# SensorRPM.net
KiCad netlist of a schematic drawn in Altium Designer
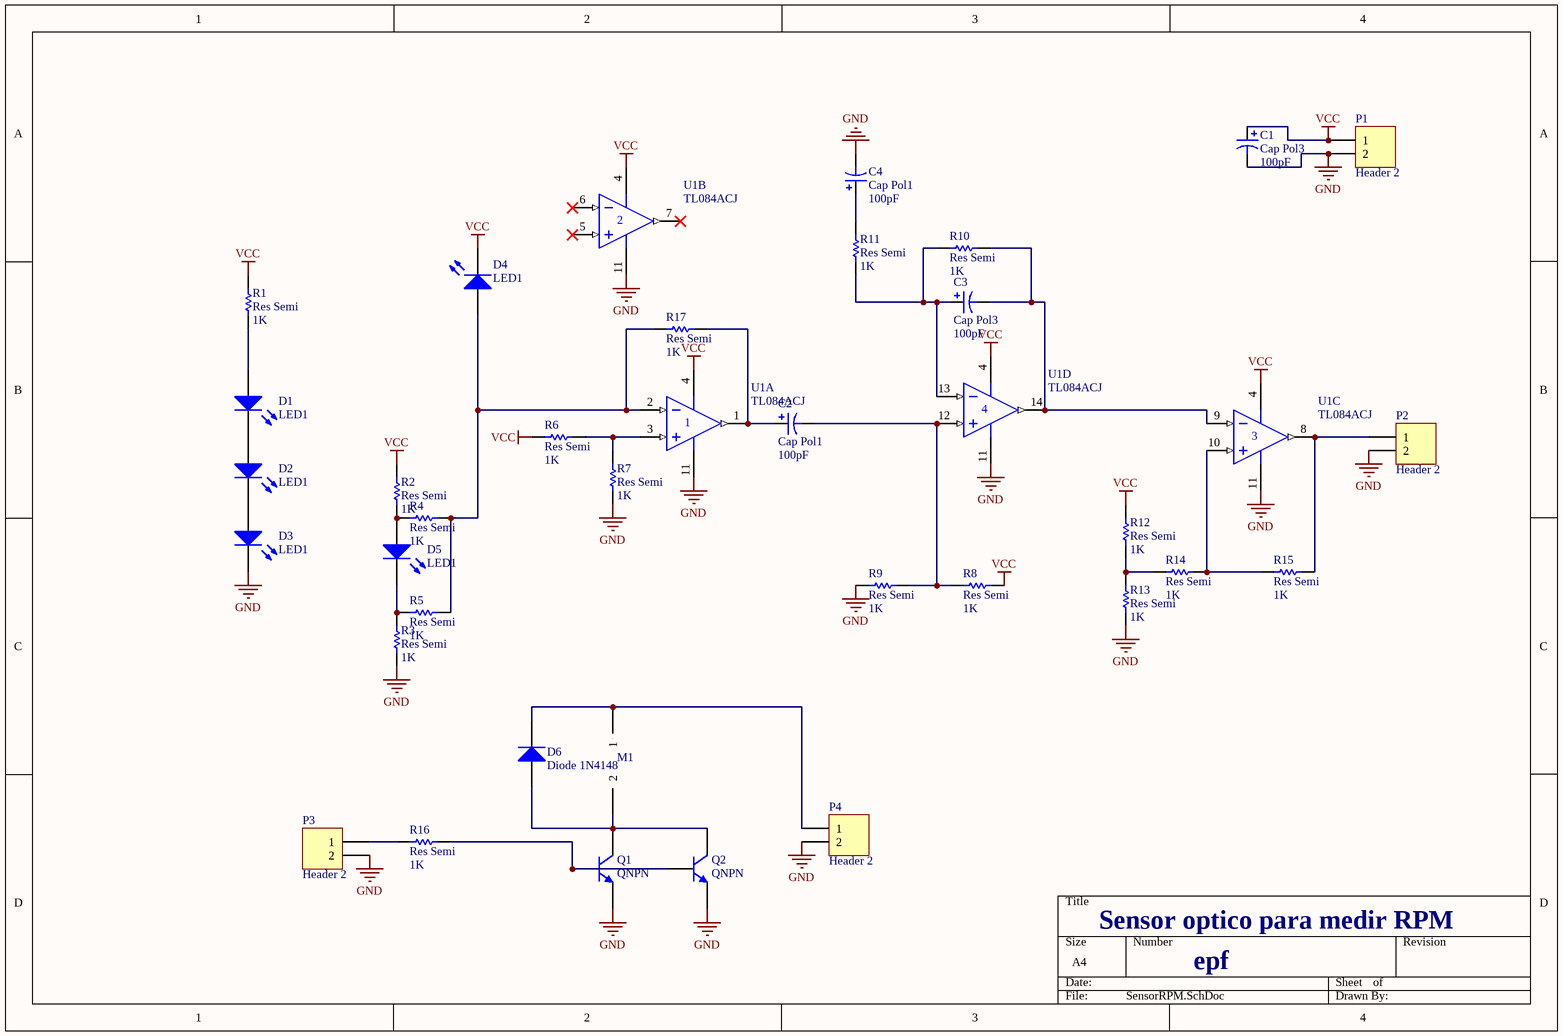
[diagram p0: SensorRPM.SchDoc]

(export (version "E")
  (design (tool "Eeschema 10.0.6"))
  (components
    (comp (ref "C1")
      (value "Cap Pol3")
      (footprint "C0805")
      (description "Polarized Capacitor (Surface Mount)")
      (fields (field (name "ALTIUM_VALUE") "100pF") (field (name "PUBLISHER") "Altium Limited"))
      (libsource (lib "Miscellaneous Devices") (part "Cap Pol3"))
    )
    (comp (ref "C2")
      (value "Cap Pol1")
      (footprint "B")
      (description "Polarized Capacitor (Radial)")
      (fields (field (name "ALTIUM_VALUE") "100pF") (field (name "PUBLISHER") "Altium Limited"))
      (libsource (lib "Miscellaneous Devices") (part "Cap Pol1"))
    )
    (comp (ref "C3")
      (value "Cap Pol3")
      (footprint "C0805")
      (description "Polarized Capacitor (Surface Mount)")
      (fields (field (name "ALTIUM_VALUE") "100pF") (field (name "PUBLISHER") "Altium Limited"))
      (libsource (lib "Miscellaneous Devices") (part "Cap Pol3"))
    )
    (comp (ref "C4")
      (value "Cap Pol1")
      (footprint "B")
      (description "Polarized Capacitor (Radial)")
      (fields (field (name "ALTIUM_VALUE") "100pF") (field (name "PUBLISHER") "Altium Limited"))
      (libsource (lib "Miscellaneous Devices") (part "Cap Pol1"))
    )
    (comp (ref "D1")
      (value "LED1")
      (footprint "LED-1")
      (description "Typical RED GaAs LED")
      (fields (field (name "PUBLISHER") "Altium Limited"))
      (libsource (lib "Miscellaneous Devices") (part "LED1"))
    )
    (comp (ref "D2")
      (value "LED1")
      (footprint "LED-1")
      (description "Typical RED GaAs LED")
      (fields (field (name "PUBLISHER") "Altium Limited"))
      (libsource (lib "Miscellaneous Devices") (part "LED1"))
    )
    (comp (ref "D3")
      (value "LED1")
      (footprint "LED-1")
      (description "Typical RED GaAs LED")
      (fields (field (name "PUBLISHER") "Altium Limited"))
      (libsource (lib "Miscellaneous Devices") (part "LED1"))
    )
    (comp (ref "D4")
      (value "LED1")
      (footprint "LED-1")
      (description "Typical RED GaAs LED")
      (fields (field (name "PUBLISHER") "Altium Limited"))
      (libsource (lib "Miscellaneous Devices") (part "LED1"))
    )
    (comp (ref "D5")
      (value "LED1")
      (footprint "LED-1")
      (description "Typical RED GaAs LED")
      (fields (field (name "PUBLISHER") "Altium Limited"))
      (libsource (lib "Miscellaneous Devices") (part "LED1"))
    )
    (comp (ref "D6")
      (value "Diode 1N4148")
      (footprint "DO-35")
      (description "High Conductance Fast Diode")
      (fields (field (name "PUBLISHER") "Altium Limited"))
      (libsource (lib "Miscellaneous Devices") (part "Diode 1N4148"))
    )
    (comp (ref "M1") (value "Motor") (footprint "Motor1") (libsource (lib "epf") (part "Motor")))
    (comp (ref "P1")
      (value "Header 2")
      (footprint "HDR1X2")
      (description "Header, 2-Pin")
      (fields (field (name "PUBLISHER") "Altium Limited"))
      (libsource (lib "Miscellaneous Connectors") (part "Header 2"))
    )
    (comp (ref "P2")
      (value "Header 2")
      (footprint "HDR1X2")
      (description "Header, 2-Pin")
      (fields (field (name "PUBLISHER") "Altium Limited"))
      (libsource (lib "Miscellaneous Connectors") (part "Header 2"))
    )
    (comp (ref "P3")
      (value "Header 2")
      (footprint "HDR1X2")
      (description "Header, 2-Pin")
      (fields (field (name "PUBLISHER") "Altium Limited"))
      (libsource (lib "") (part "Header 2_1"))
    )
    (comp (ref "P4")
      (value "Header 2")
      (footprint "HDR1X2")
      (description "Header, 2-Pin")
      (fields (field (name "PUBLISHER") "Altium Limited"))
      (libsource (lib "Miscellaneous Connectors") (part "Header 2"))
    )
    (comp (ref "Q1")
      (value "QNPN")
      (footprint "SOT-23B")
      (description "NPN Bipolar Transistor")
      (fields (field (name "PUBLISHER") "Altium Limited"))
      (libsource (lib "Miscellaneous Devices") (part "QNPN"))
    )
    (comp (ref "Q2")
      (value "QNPN")
      (footprint "SOT-23B")
      (description "NPN Bipolar Transistor")
      (fields (field (name "PUBLISHER") "Altium Limited"))
      (libsource (lib "Miscellaneous Devices") (part "QNPN"))
    )
    (comp (ref "R1")
      (value "Res Semi")
      (footprint "2012[0805]")
      (description "Semiconductor Resistor")
      (fields (field (name "ALTIUM_VALUE") "1K") (field (name "PUBLISHER") "Altium Limited"))
      (libsource (lib "Miscellaneous Devices") (part "Res Semi"))
    )
    (comp (ref "R2")
      (value "Res Semi")
      (footprint "2012[0805]")
      (description "Semiconductor Resistor")
      (fields (field (name "ALTIUM_VALUE") "1K") (field (name "PUBLISHER") "Altium Limited"))
      (libsource (lib "Miscellaneous Devices") (part "Res Semi"))
    )
    (comp (ref "R3")
      (value "Res Semi")
      (footprint "2012[0805]")
      (description "Semiconductor Resistor")
      (fields (field (name "ALTIUM_VALUE") "1K") (field (name "PUBLISHER") "Altium Limited"))
      (libsource (lib "Miscellaneous Devices") (part "Res Semi"))
    )
    (comp (ref "R4")
      (value "Res Semi")
      (footprint "2012[0805]")
      (description "Semiconductor Resistor")
      (fields (field (name "ALTIUM_VALUE") "1K") (field (name "PUBLISHER") "Altium Limited"))
      (libsource (lib "Miscellaneous Devices") (part "Res Semi"))
    )
    (comp (ref "R5")
      (value "Res Semi")
      (footprint "2012[0805]")
      (description "Semiconductor Resistor")
      (fields (field (name "ALTIUM_VALUE") "1K") (field (name "PUBLISHER") "Altium Limited"))
      (libsource (lib "Miscellaneous Devices") (part "Res Semi"))
    )
    (comp (ref "R6")
      (value "Res Semi")
      (footprint "2012[0805]")
      (description "Semiconductor Resistor")
      (fields (field (name "ALTIUM_VALUE") "1K") (field (name "PUBLISHER") "Altium Limited"))
      (libsource (lib "Miscellaneous Devices") (part "Res Semi"))
    )
    (comp (ref "R7")
      (value "Res Semi")
      (footprint "2012[0805]")
      (description "Semiconductor Resistor")
      (fields (field (name "ALTIUM_VALUE") "1K") (field (name "PUBLISHER") "Altium Limited"))
      (libsource (lib "Miscellaneous Devices") (part "Res Semi"))
    )
    (comp (ref "R8")
      (value "Res Semi")
      (footprint "2012[0805]")
      (description "Semiconductor Resistor")
      (fields (field (name "ALTIUM_VALUE") "1K") (field (name "PUBLISHER") "Altium Limited"))
      (libsource (lib "Miscellaneous Devices") (part "Res Semi"))
    )
    (comp (ref "R9")
      (value "Res Semi")
      (footprint "2012[0805]")
      (description "Semiconductor Resistor")
      (fields (field (name "ALTIUM_VALUE") "1K") (field (name "PUBLISHER") "Altium Limited"))
      (libsource (lib "Miscellaneous Devices") (part "Res Semi"))
    )
    (comp (ref "R10")
      (value "Res Semi")
      (footprint "2012[0805]")
      (description "Semiconductor Resistor")
      (fields (field (name "ALTIUM_VALUE") "1K") (field (name "PUBLISHER") "Altium Limited"))
      (libsource (lib "Miscellaneous Devices") (part "Res Semi"))
    )
    (comp (ref "R11")
      (value "Res Semi")
      (footprint "2012[0805]")
      (description "Semiconductor Resistor")
      (fields (field (name "ALTIUM_VALUE") "1K") (field (name "PUBLISHER") "Altium Limited"))
      (libsource (lib "Miscellaneous Devices") (part "Res Semi"))
    )
    (comp (ref "R12")
      (value "Res Semi")
      (footprint "2012[0805]")
      (description "Semiconductor Resistor")
      (fields (field (name "ALTIUM_VALUE") "1K") (field (name "PUBLISHER") "Altium Limited"))
      (libsource (lib "Miscellaneous Devices") (part "Res Semi"))
    )
    (comp (ref "R13")
      (value "Res Semi")
      (footprint "2012[0805]")
      (description "Semiconductor Resistor")
      (fields (field (name "ALTIUM_VALUE") "1K") (field (name "PUBLISHER") "Altium Limited"))
      (libsource (lib "Miscellaneous Devices") (part "Res Semi"))
    )
    (comp (ref "R14")
      (value "Res Semi")
      (footprint "2012[0805]")
      (description "Semiconductor Resistor")
      (fields (field (name "ALTIUM_VALUE") "1K") (field (name "PUBLISHER") "Altium Limited"))
      (libsource (lib "Miscellaneous Devices") (part "Res Semi"))
    )
    (comp (ref "R15")
      (value "Res Semi")
      (footprint "2012[0805]")
      (description "Semiconductor Resistor")
      (fields (field (name "ALTIUM_VALUE") "1K") (field (name "PUBLISHER") "Altium Limited"))
      (libsource (lib "Miscellaneous Devices") (part "Res Semi"))
    )
    (comp (ref "R16")
      (value "Res Semi")
      (footprint "2012[0805]")
      (description "Semiconductor Resistor")
      (fields (field (name "ALTIUM_VALUE") "1K") (field (name "PUBLISHER") "Altium Limited"))
      (libsource (lib "Miscellaneous Devices") (part "Res Semi"))
    )
    (comp (ref "R17")
      (value "Res Semi")
      (footprint "2012[0805]")
      (description "Semiconductor Resistor")
      (fields (field (name "ALTIUM_VALUE") "1K") (field (name "PUBLISHER") "Altium Limited"))
      (libsource (lib "Miscellaneous Devices") (part "Res Semi"))
    )
    (comp (ref "U1")
      (value "TL084ACJ")
      (footprint "632-08")
      (description "JFET-Input Operational Amplifier")
      (fields (field (name "PUBLISHER") "Altium Limited"))
      (libsource (lib "Motorola Amplifier Operational Amplifier") (part "TL084ACJ"))
    )
  )
  (nets
    (net (code "1") (name "GND") (class "Default")
      (node (ref "C1") (pin "2") (pinfunction "2_2") (pintype "passive"))
      (node (ref "C4") (pin "2") (pinfunction "2_2") (pintype "passive"))
      (node (ref "D3") (pin "2") (pinfunction "K_2") (pintype "passive"))
      (node (ref "P1") (pin "2") (pinfunction "2_2") (pintype "passive"))
      (node (ref "P2") (pin "2") (pinfunction "2_2") (pintype "passive"))
      (node (ref "P3") (pin "2") (pinfunction "2_2") (pintype "passive"))
      (node (ref "P4") (pin "2") (pinfunction "2_2") (pintype "passive"))
      (node (ref "Q1") (pin "3") (pinfunction "E_3") (pintype "passive"))
      (node (ref "Q2") (pin "3") (pinfunction "E_3") (pintype "passive"))
      (node (ref "R13") (pin "2") (pinfunction "2_2") (pintype "passive"))
      (node (ref "R3") (pin "1") (pinfunction "1_1") (pintype "passive"))
      (node (ref "R7") (pin "2") (pinfunction "2_2") (pintype "passive"))
      (node (ref "R9") (pin "1") (pinfunction "1_1") (pintype "passive"))
      (node (ref "U1") (pin "11") (pinfunction "V-_11") (pintype "power_in"))
    )
    (net (code "2") (name "Net-(C4-Pad1)") (class "Default")
      (node (ref "C4") (pin "1") (pinfunction "1_1") (pintype "passive"))
      (node (ref "R11") (pin "1") (pinfunction "1_1") (pintype "passive"))
    )
    (net (code "3") (name "Net-(D1-A)") (class "Default")
      (node (ref "D1") (pin "1") (pinfunction "A_1") (pintype "passive"))
      (node (ref "R1") (pin "1") (pinfunction "1_1") (pintype "passive"))
    )
    (net (code "4") (name "Net-(D1-K)") (class "Default")
      (node (ref "D1") (pin "2") (pinfunction "K_2") (pintype "passive"))
      (node (ref "D2") (pin "1") (pinfunction "A_1") (pintype "passive"))
    )
    (net (code "5") (name "Net-(D2-K)") (class "Default")
      (node (ref "D2") (pin "2") (pinfunction "K_2") (pintype "passive"))
      (node (ref "D3") (pin "1") (pinfunction "A_1") (pintype "passive"))
    )
    (net (code "6") (name "Net-(D4-A)") (class "Default")
      (node (ref "D4") (pin "1") (pinfunction "A_1") (pintype "passive"))
      (node (ref "R17") (pin "1") (pinfunction "1_1") (pintype "passive"))
      (node (ref "R4") (pin "1") (pinfunction "1_1") (pintype "passive"))
      (node (ref "R5") (pin "1") (pinfunction "1_1") (pintype "passive"))
      (node (ref "U1") (pin "2") (pinfunction "IN-_2") (pintype "input"))
    )
    (net (code "7") (name "Net-(D5-A)") (class "Default")
      (node (ref "D5") (pin "1") (pinfunction "A_1") (pintype "passive"))
      (node (ref "R2") (pin "1") (pinfunction "1_1") (pintype "passive"))
      (node (ref "R4") (pin "2") (pinfunction "2_2") (pintype "passive"))
    )
    (net (code "8") (name "Net-(D5-K)") (class "Default")
      (node (ref "D5") (pin "2") (pinfunction "K_2") (pintype "passive"))
      (node (ref "R3") (pin "2") (pinfunction "2_2") (pintype "passive"))
      (node (ref "R5") (pin "2") (pinfunction "2_2") (pintype "passive"))
    )
    (net (code "9") (name "Net-(D6-A)") (class "Default")
      (node (ref "D6") (pin "1") (pinfunction "A_1") (pintype "passive"))
      (node (ref "M1") (pin "2") (pinfunction "2_2") (pintype "passive"))
      (node (ref "Q1") (pin "1") (pinfunction "C_1") (pintype "passive"))
      (node (ref "Q2") (pin "1") (pinfunction "C_1") (pintype "passive"))
    )
    (net (code "10") (name "Net-(D6-K)") (class "Default")
      (node (ref "D6") (pin "2") (pinfunction "K_2") (pintype "passive"))
      (node (ref "M1") (pin "1") (pinfunction "1_1") (pintype "passive"))
      (node (ref "P4") (pin "1") (pinfunction "1_1") (pintype "passive"))
    )
    (net (code "11") (name "Net-(P3-Pad1)") (class "Default")
      (node (ref "P3") (pin "1") (pinfunction "1_1") (pintype "passive"))
      (node (ref "R16") (pin "1") (pinfunction "1_1") (pintype "passive"))
    )
    (net (code "12") (name "Net-(Q1-B)") (class "Default")
      (node (ref "Q1") (pin "2") (pinfunction "B_2") (pintype "passive"))
      (node (ref "Q2") (pin "2") (pinfunction "B_2") (pintype "passive"))
      (node (ref "R16") (pin "2") (pinfunction "2_2") (pintype "passive"))
    )
    (net (code "13") (name "Net-(R12-Pad2)") (class "Default")
      (node (ref "R12") (pin "2") (pinfunction "2_2") (pintype "passive"))
      (node (ref "R13") (pin "1") (pinfunction "1_1") (pintype "passive"))
      (node (ref "R14") (pin "1") (pinfunction "1_1") (pintype "passive"))
    )
    (net (code "14") (name "Net-(U1A-IN+)") (class "Default")
      (node (ref "R6") (pin "1") (pinfunction "1_1") (pintype "passive"))
      (node (ref "R7") (pin "1") (pinfunction "1_1") (pintype "passive"))
      (node (ref "U1") (pin "3") (pinfunction "IN+_3") (pintype "input"))
    )
    (net (code "15") (name "Net-(U1A-OUT)") (class "Default")
      (node (ref "C2") (pin "1") (pinfunction "1_1") (pintype "passive"))
      (node (ref "R17") (pin "2") (pinfunction "2_2") (pintype "passive"))
      (node (ref "U1") (pin "1") (pinfunction "OUT_1") (pintype "output"))
    )
    (net (code "16") (name "Net-(U1C-IN+)") (class "Default")
      (node (ref "R14") (pin "2") (pinfunction "2_2") (pintype "passive"))
      (node (ref "R15") (pin "1") (pinfunction "1_1") (pintype "passive"))
      (node (ref "U1") (pin "10") (pinfunction "IN+_10") (pintype "input"))
    )
    (net (code "17") (name "Net-(U1C-IN-)") (class "Default")
      (node (ref "C3") (pin "2") (pinfunction "2_2") (pintype "passive"))
      (node (ref "R10") (pin "2") (pinfunction "2_2") (pintype "passive"))
      (node (ref "U1") (pin "14") (pinfunction "OUT_14") (pintype "output"))
      (node (ref "U1") (pin "9") (pinfunction "IN-_9") (pintype "input"))
    )
    (net (code "18") (name "Net-(U1C-OUT)") (class "Default")
      (node (ref "P2") (pin "1") (pinfunction "1_1") (pintype "passive"))
      (node (ref "R15") (pin "2") (pinfunction "2_2") (pintype "passive"))
      (node (ref "U1") (pin "8") (pinfunction "OUT_8") (pintype "output"))
    )
    (net (code "19") (name "Net-(U1D-IN+)") (class "Default")
      (node (ref "C2") (pin "2") (pinfunction "2_2") (pintype "passive"))
      (node (ref "R8") (pin "1") (pinfunction "1_1") (pintype "passive"))
      (node (ref "R9") (pin "2") (pinfunction "2_2") (pintype "passive"))
      (node (ref "U1") (pin "12") (pinfunction "IN+_12") (pintype "input"))
    )
    (net (code "20") (name "Net-(U1D-IN-)") (class "Default")
      (node (ref "C3") (pin "1") (pinfunction "1_1") (pintype "passive"))
      (node (ref "R10") (pin "1") (pinfunction "1_1") (pintype "passive"))
      (node (ref "R11") (pin "2") (pinfunction "2_2") (pintype "passive"))
      (node (ref "U1") (pin "13") (pinfunction "IN-_13") (pintype "input"))
    )
    (net (code "21") (name "VCC") (class "Default")
      (node (ref "C1") (pin "1") (pinfunction "1_1") (pintype "passive"))
      (node (ref "D4") (pin "2") (pinfunction "K_2") (pintype "passive"))
      (node (ref "P1") (pin "1") (pinfunction "1_1") (pintype "passive"))
      (node (ref "R1") (pin "2") (pinfunction "2_2") (pintype "passive"))
      (node (ref "R12") (pin "1") (pinfunction "1_1") (pintype "passive"))
      (node (ref "R2") (pin "2") (pinfunction "2_2") (pintype "passive"))
      (node (ref "R6") (pin "2") (pinfunction "2_2") (pintype "passive"))
      (node (ref "R8") (pin "2") (pinfunction "2_2") (pintype "passive"))
      (node (ref "U1") (pin "4") (pinfunction "V+_4") (pintype "power_in"))
    )
    (net (code "22") (name "unconnected-(U1B-IN+-Pad5)") (class "Default")
      (node (ref "U1") (pin "5") (pinfunction "IN+_5") (pintype "input+no_connect"))
    )
    (net (code "23") (name "unconnected-(U1B-IN--Pad6)") (class "Default")
      (node (ref "U1") (pin "6") (pinfunction "IN-_6") (pintype "input+no_connect"))
    )
    (net (code "24") (name "unconnected-(U1B-OUT-Pad7)") (class "Default")
      (node (ref "U1") (pin "7") (pinfunction "OUT_7") (pintype "output+no_connect"))
    )
  )
)
